# ESP_NeoPixel.net
KiCad netlist of a schematic drawn in EAGLE
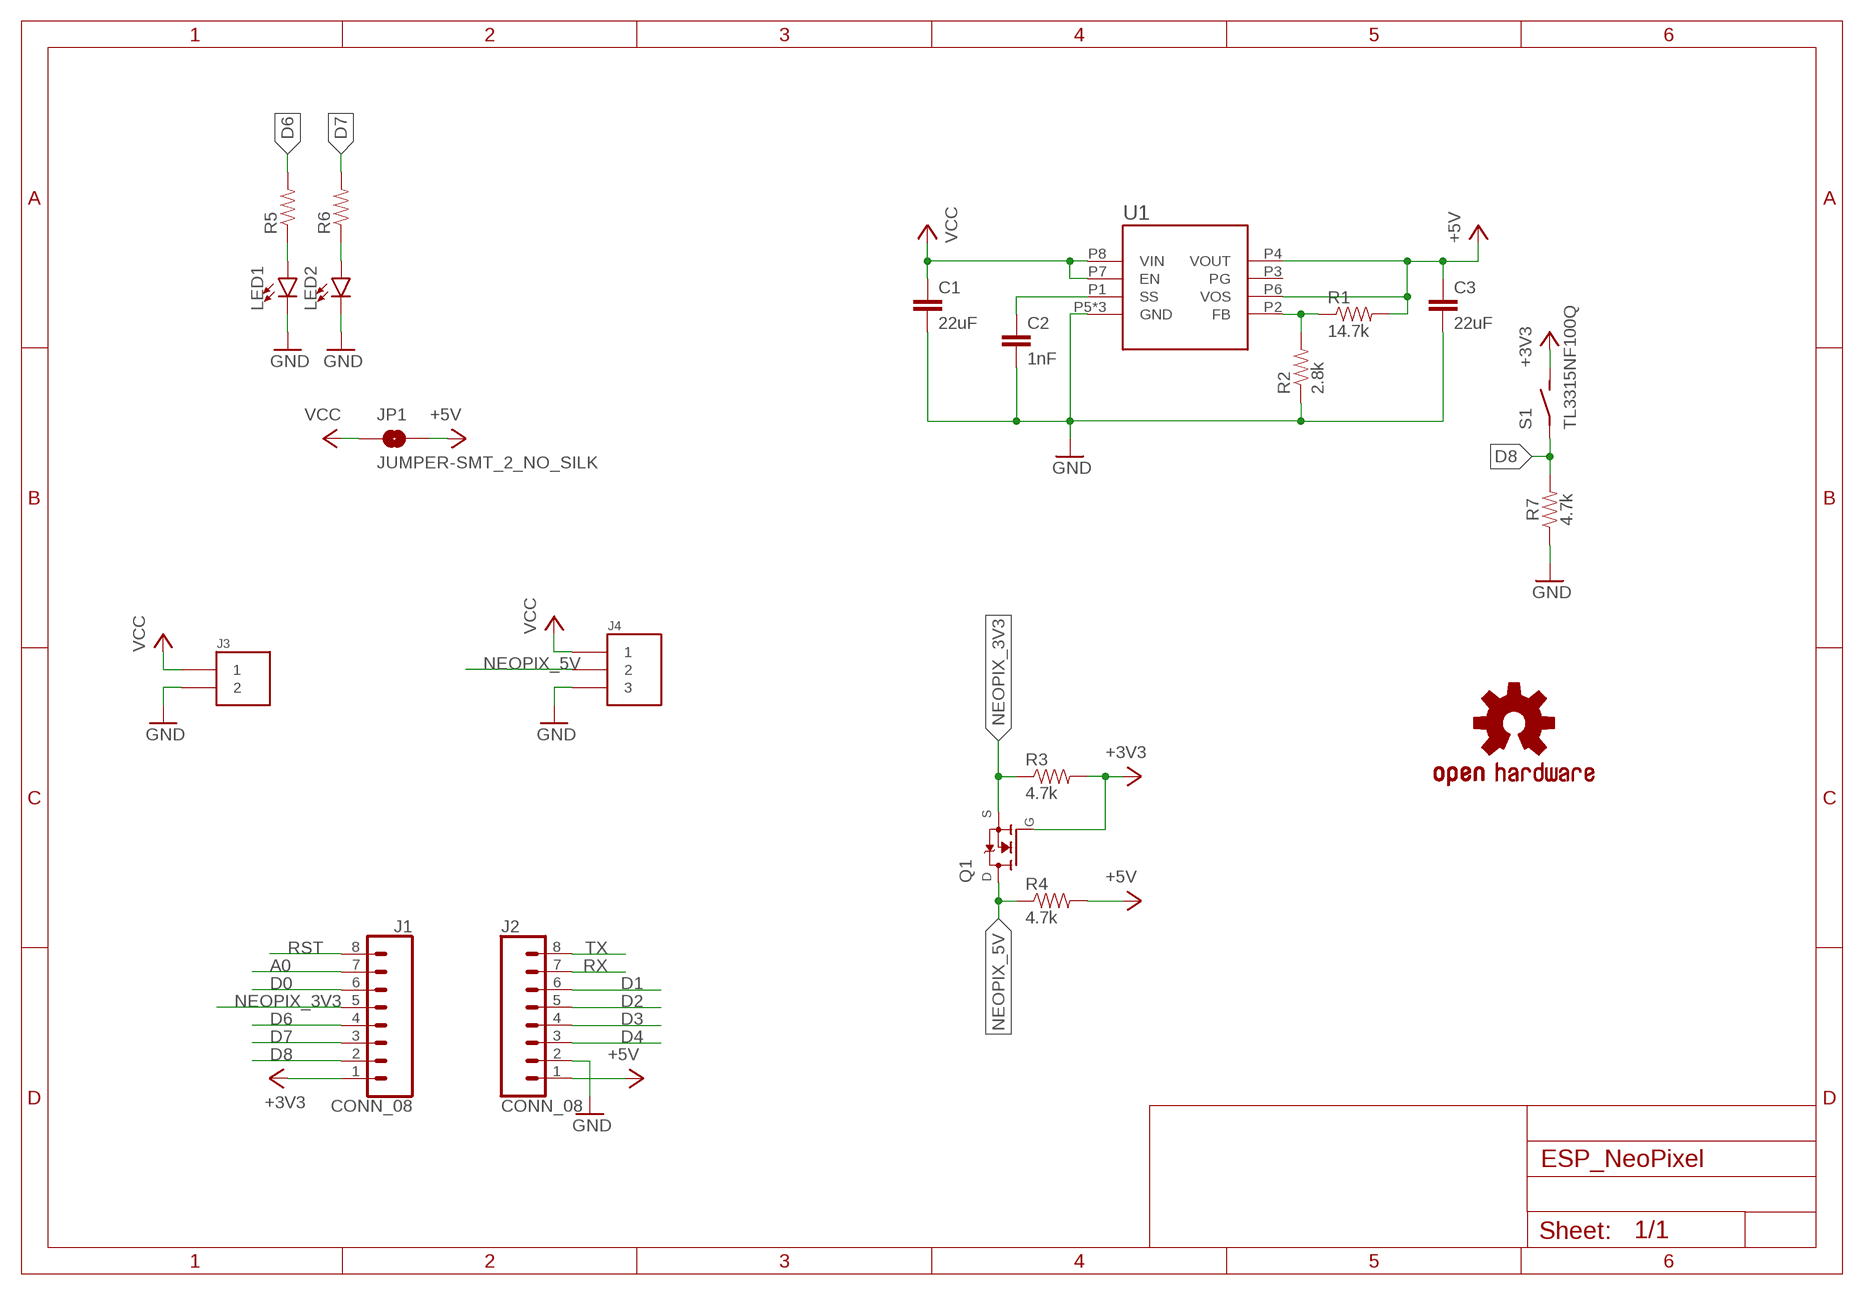
[diagram p0: schematic, sheet 1]

(export (version "E")
  (design (tool "Eeschema 10.0.6"))
  (components
    (comp (ref "C1")
      (value "22uF")
      (footprint "eagle-import:0805")
      (libsource (lib "eagle-import") (part "22UF-0805-6.3V-20%"))
    )
    (comp (ref "C2")
      (value "1nF")
      (footprint "eagle-import:0603")
      (libsource (lib "eagle-import") (part "1.0NF/1000PF-0603-50V-10%"))
    )
    (comp (ref "C3")
      (value "22uF")
      (footprint "eagle-import:0805")
      (libsource (lib "eagle-import") (part "22UF-0805-6.3V-20%"))
    )
    (comp (ref "J1")
      (value "CONN_08")
      (footprint "eagle-import:1X08_LOCK_NO_SILK")
      (libsource (lib "eagle-import") (part "CONN_08"))
    )
    (comp (ref "J2")
      (value "CONN_08")
      (footprint "eagle-import:1X08_LOCK_NO_SILK")
      (libsource (lib "eagle-import") (part "CONN_08"))
    )
    (comp (ref "J3")
      (value "MKDS3-2-5.00")
      (footprint "eagle-import:MKDS3-2-5.00")
      (libsource (lib "eagle-import") (part "MKDS3-2-5.00"))
    )
    (comp (ref "J4")
      (value "MKDS3-3-5.00")
      (footprint "eagle-import:MKDS3-3-5.00")
      (libsource (lib "eagle-import") (part "MKDS3-3-5.00"))
    )
    (comp (ref "JP1")
      (value "JUMPER-SMT_2_NO_SILK")
      (footprint "eagle-import:SMT-JUMPER_2_NO_SILK")
      (libsource (lib "eagle-import") (part "JUMPER-SMT_2_NO_SILK"))
    )
    (comp (ref "LED1")
      (value "LED0603")
      (footprint "eagle-import:LED-0603")
      (libsource (lib "eagle-import") (part "LED0603"))
    )
    (comp (ref "LED2")
      (value "LED0603")
      (footprint "eagle-import:LED-0603")
      (libsource (lib "eagle-import") (part "LED0603"))
    )
    (comp (ref "LOGO1")
      (value "OSHW-LOGOS")
      (footprint "eagle-import:OSHW-LOGO-S")
      (libsource (lib "eagle-import") (part "OSHW-LOGOS"))
    )
    (comp (ref "Q1")
      (value "BSN20,215")
      (footprint "eagle-import:BSN20_215")
      (fields (field (name "MF") "NXP Semiconductors"))
      (libsource (lib "eagle-import") (part "BSN20,215"))
    )
    (comp (ref "R1")
      (value "14.7k")
      (footprint "eagle-import:0603")
      (libsource (lib "eagle-import") (part "RESISTOR0603"))
    )
    (comp (ref "R2")
      (value "2.8k")
      (footprint "eagle-import:0603")
      (libsource (lib "eagle-import") (part "RESISTOR0603"))
    )
    (comp (ref "R3")
      (value "4.7k")
      (footprint "eagle-import:0603")
      (libsource (lib "eagle-import") (part "4.7KOHM-0603-1/10W-1%"))
    )
    (comp (ref "R4")
      (value "4.7k")
      (footprint "eagle-import:0603")
      (libsource (lib "eagle-import") (part "4.7KOHM-0603-1/10W-1%"))
    )
    (comp (ref "R5")
      (value "RESISTOR0603")
      (footprint "eagle-import:0603")
      (libsource (lib "eagle-import") (part "RESISTOR0603"))
    )
    (comp (ref "R6")
      (value "RESISTOR0603")
      (footprint "eagle-import:0603")
      (libsource (lib "eagle-import") (part "RESISTOR0603"))
    )
    (comp (ref "R7")
      (value "4.7k")
      (footprint "eagle-import:0603")
      (libsource (lib "eagle-import") (part "RESISTOR0603"))
    )
    (comp (ref "S1")
      (value "TL3315NF100Q")
      (footprint "eagle-import:TL3315NF100Q")
      (libsource (lib "eagle-import") (part "TL3315NF100Q"))
    )
    (comp (ref "U1")
      (value "LMZ21700")
      (footprint "eagle-import:SIL0008E")
      (libsource (lib "eagle-import") (part "LMZ21700"))
    )
  )
  (nets
    (net (code "1") (name "+3V3") (class "Default")
      (node (ref "J1") (pin "1") (pinfunction "1_1") (pintype "passive"))
      (node (ref "Q1") (pin "1") (pinfunction "G_1") (pintype "passive"))
      (node (ref "R3") (pin "2") (pinfunction "2_2") (pintype "passive"))
      (node (ref "S1") (pin "P3") (pinfunction "S_P3") (pintype "passive"))
      (node (ref "S1") (pin "P4") (pinfunction "S_P4") (pintype "passive"))
    )
    (net (code "2") (name "+5V") (class "Default")
      (node (ref "C3") (pin "1") (pinfunction "1_1") (pintype "passive"))
      (node (ref "J2") (pin "1") (pinfunction "1_1") (pintype "passive"))
      (node (ref "JP1") (pin "2") (pinfunction "2_2") (pintype "passive"))
      (node (ref "R1") (pin "2") (pinfunction "2_2") (pintype "passive"))
      (node (ref "R4") (pin "2") (pinfunction "2_2") (pintype "passive"))
      (node (ref "U1") (pin "P4") (pinfunction "VOUT_P4") (pintype "bidirectional"))
      (node (ref "U1") (pin "P6") (pinfunction "VOS_P6") (pintype "bidirectional"))
    )
    (net (code "3") (name "/A0") (class "Default")
      (node (ref "J1") (pin "7") (pinfunction "7_7") (pintype "passive"))
    )
    (net (code "4") (name "/D0") (class "Default")
      (node (ref "J1") (pin "6") (pinfunction "6_6") (pintype "passive"))
    )
    (net (code "5") (name "/D1") (class "Default")
      (node (ref "J2") (pin "6") (pinfunction "6_6") (pintype "passive"))
    )
    (net (code "6") (name "/D2") (class "Default")
      (node (ref "J2") (pin "5") (pinfunction "5_5") (pintype "passive"))
    )
    (net (code "7") (name "/D3") (class "Default")
      (node (ref "J2") (pin "4") (pinfunction "4_4") (pintype "passive"))
    )
    (net (code "8") (name "/D4") (class "Default")
      (node (ref "J2") (pin "3") (pinfunction "3_3") (pintype "passive"))
    )
    (net (code "9") (name "/RST") (class "Default")
      (node (ref "J1") (pin "8") (pinfunction "8_8") (pintype "passive"))
    )
    (net (code "10") (name "/RX") (class "Default")
      (node (ref "J2") (pin "7") (pinfunction "7_7") (pintype "passive"))
    )
    (net (code "11") (name "/TX") (class "Default")
      (node (ref "J2") (pin "8") (pinfunction "8_8") (pintype "passive"))
    )
    (net (code "12") (name "D6") (class "Default")
      (node (ref "J1") (pin "4") (pinfunction "4_4") (pintype "passive"))
      (node (ref "R5") (pin "2") (pinfunction "2_2") (pintype "passive"))
    )
    (net (code "13") (name "D7") (class "Default")
      (node (ref "J1") (pin "3") (pinfunction "3_3") (pintype "passive"))
      (node (ref "R6") (pin "2") (pinfunction "2_2") (pintype "passive"))
    )
    (net (code "14") (name "D8") (class "Default")
      (node (ref "J1") (pin "2") (pinfunction "2_2") (pintype "passive"))
      (node (ref "R7") (pin "2") (pinfunction "2_2") (pintype "passive"))
      (node (ref "S1") (pin "P1") (pinfunction "P_P1") (pintype "passive"))
      (node (ref "S1") (pin "P2") (pinfunction "P_P2") (pintype "passive"))
    )
    (net (code "15") (name "GND") (class "Default")
      (node (ref "C1") (pin "2") (pinfunction "2_2") (pintype "passive"))
      (node (ref "C2") (pin "2") (pinfunction "2_2") (pintype "passive"))
      (node (ref "C3") (pin "2") (pinfunction "2_2") (pintype "passive"))
      (node (ref "J2") (pin "2") (pinfunction "2_2") (pintype "passive"))
      (node (ref "J3") (pin "2") (pinfunction "2_2") (pintype "bidirectional"))
      (node (ref "J4") (pin "3") (pinfunction "3_3") (pintype "bidirectional"))
      (node (ref "LED1") (pin "C") (pinfunction "C_C") (pintype "passive"))
      (node (ref "LED2") (pin "C") (pinfunction "C_C") (pintype "passive"))
      (node (ref "R2") (pin "1") (pinfunction "1_1") (pintype "passive"))
      (node (ref "R7") (pin "1") (pinfunction "1_1") (pintype "passive"))
      (node (ref "U1") (pin "P10") (pinfunction "GND_P10") (pintype "bidirectional"))
      (node (ref "U1") (pin "P5") (pinfunction "GND_P5") (pintype "bidirectional"))
      (node (ref "U1") (pin "P9") (pinfunction "GND_P9") (pintype "bidirectional"))
    )
    (net (code "16") (name "NEOPIX_3V3") (class "Default")
      (node (ref "J1") (pin "5") (pinfunction "5_5") (pintype "passive"))
      (node (ref "Q1") (pin "2") (pinfunction "S_2") (pintype "passive"))
      (node (ref "R3") (pin "1") (pinfunction "1_1") (pintype "passive"))
    )
    (net (code "17") (name "NEOPIX_5V") (class "Default")
      (node (ref "J4") (pin "2") (pinfunction "2_2") (pintype "bidirectional"))
      (node (ref "Q1") (pin "3") (pinfunction "D_3") (pintype "passive"))
      (node (ref "R4") (pin "1") (pinfunction "1_1") (pintype "passive"))
    )
    (net (code "18") (name "Net-(LED1-PadA)") (class "Default")
      (node (ref "LED1") (pin "A") (pinfunction "A_A") (pintype "passive"))
      (node (ref "R5") (pin "1") (pinfunction "1_1") (pintype "passive"))
    )
    (net (code "19") (name "Net-(LED2-PadA)") (class "Default")
      (node (ref "LED2") (pin "A") (pinfunction "A_A") (pintype "passive"))
      (node (ref "R6") (pin "1") (pinfunction "1_1") (pintype "passive"))
    )
    (net (code "20") (name "Net-(U1-FB)") (class "Default")
      (node (ref "R1") (pin "1") (pinfunction "1_1") (pintype "passive"))
      (node (ref "R2") (pin "2") (pinfunction "2_2") (pintype "passive"))
      (node (ref "U1") (pin "P2") (pinfunction "FB_P2") (pintype "bidirectional"))
    )
    (net (code "21") (name "Net-(U1-SS)") (class "Default")
      (node (ref "C2") (pin "1") (pinfunction "1_1") (pintype "passive"))
      (node (ref "U1") (pin "P1") (pinfunction "SS_P1") (pintype "bidirectional"))
    )
    (net (code "22") (name "VCC") (class "Default")
      (node (ref "C1") (pin "1") (pinfunction "1_1") (pintype "passive"))
      (node (ref "J3") (pin "1") (pinfunction "1_1") (pintype "bidirectional"))
      (node (ref "J4") (pin "1") (pinfunction "1_1") (pintype "bidirectional"))
      (node (ref "JP1") (pin "1") (pinfunction "1_1") (pintype "passive"))
      (node (ref "U1") (pin "P7") (pinfunction "EN_P7") (pintype "bidirectional"))
      (node (ref "U1") (pin "P8") (pinfunction "VIN_P8") (pintype "bidirectional"))
    )
    (net (code "23") (name "unconnected-(U1-PG-PadP3)") (class "Default")
      (node (ref "U1") (pin "P3") (pinfunction "PG_P3") (pintype "bidirectional"))
    )
  )
)
